# autofowl.net
KiCad netlist of a schematic drawn in EAGLE
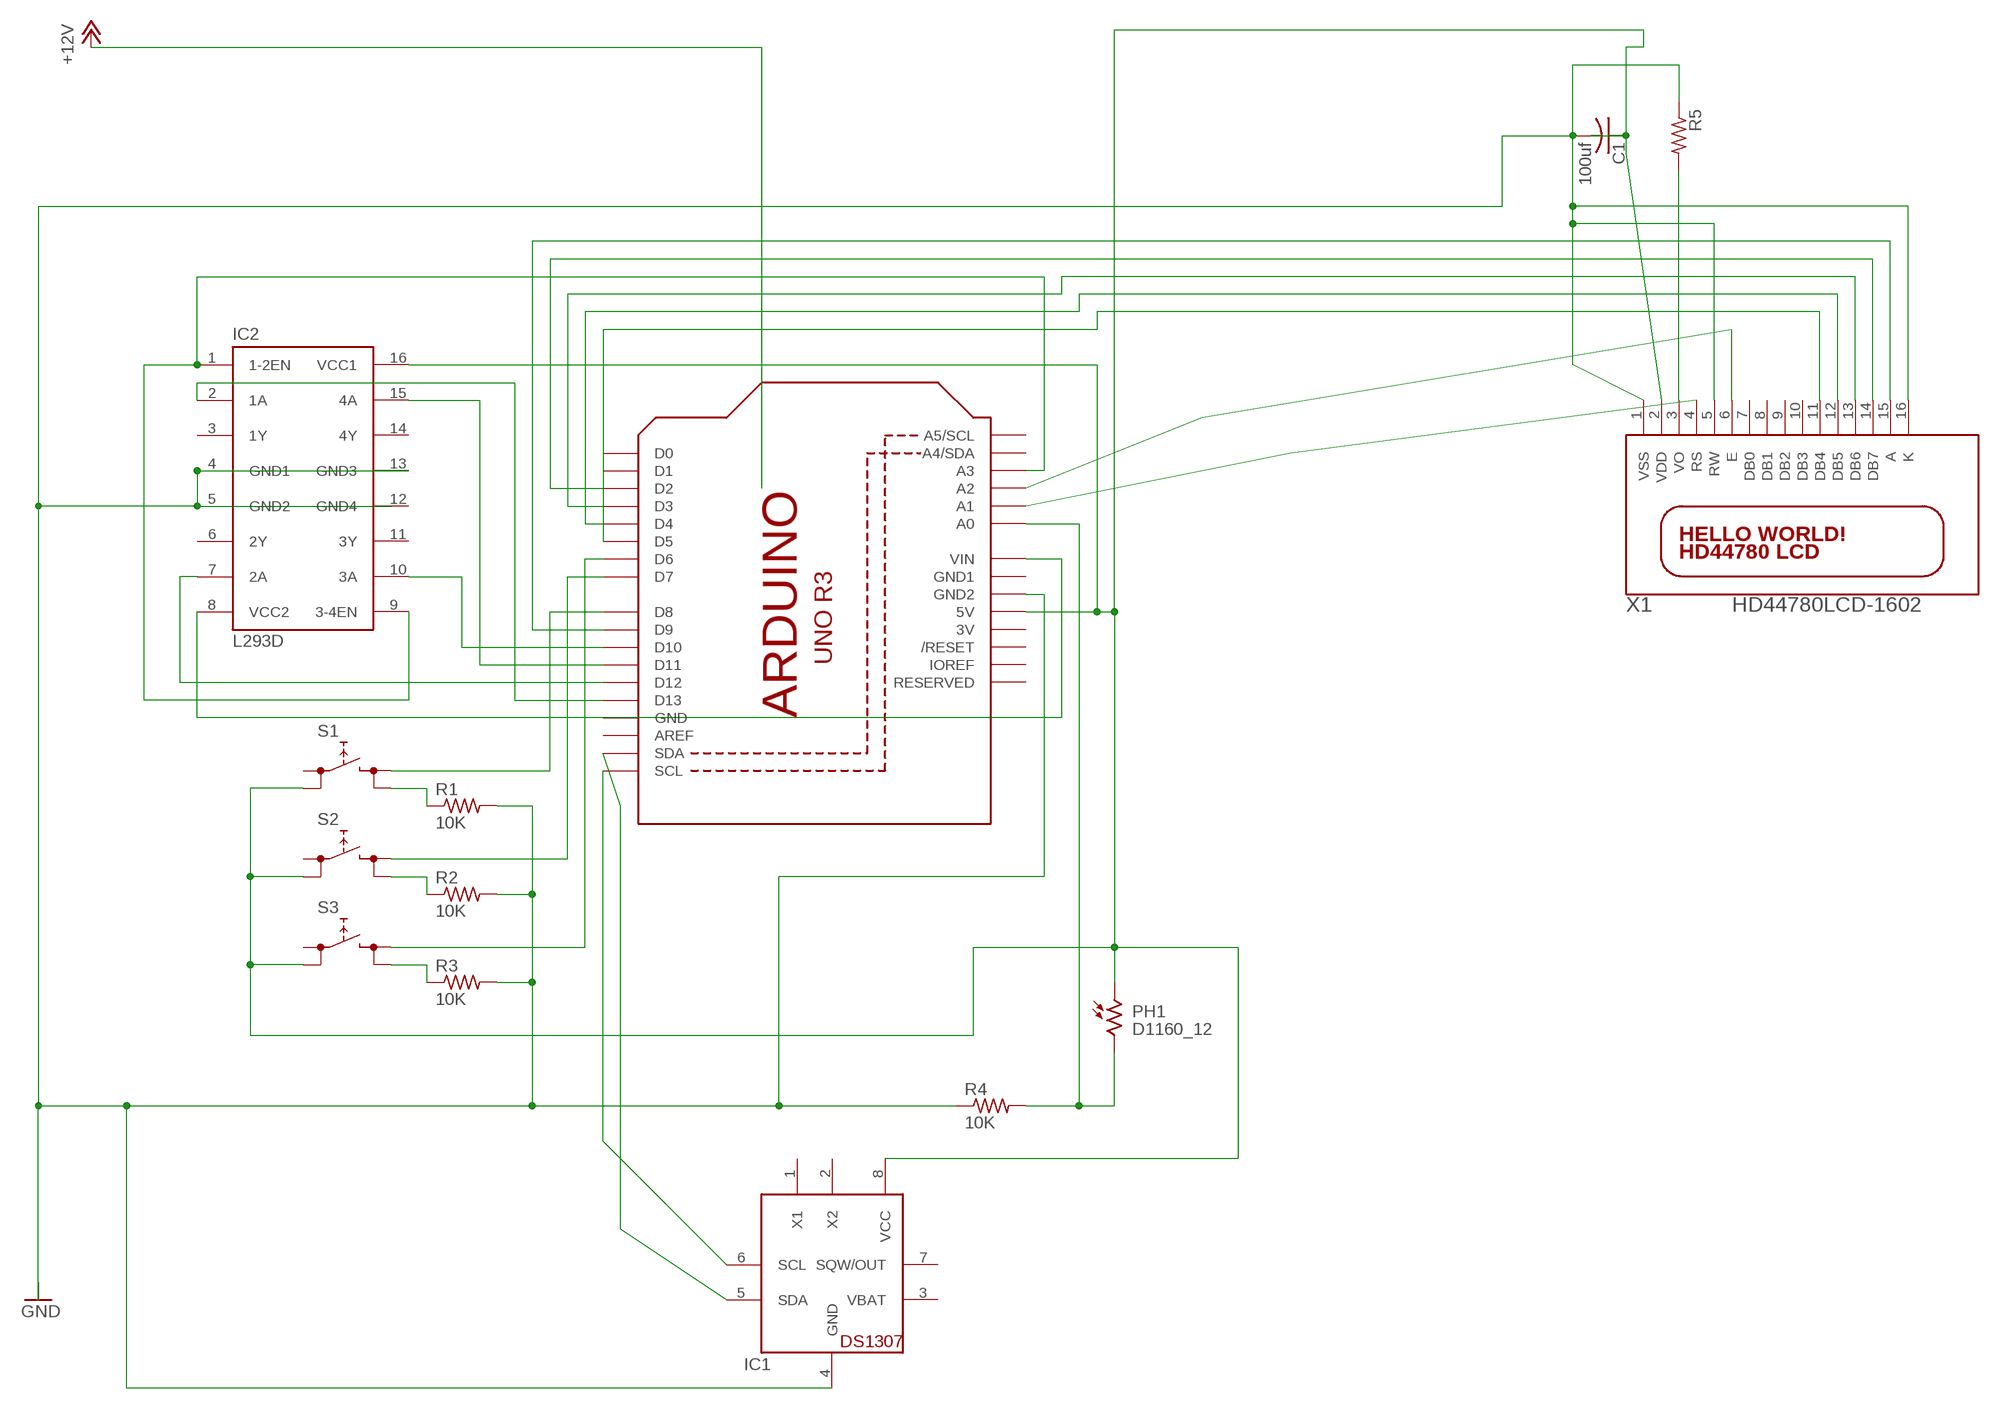
[diagram p0: schematic, sheet 1]

(export (version "E")
  (design (tool "Eeschema 10.0.6"))
  (components
    (comp (ref "C1")
      (value "100uf")
      (footprint "eagle-import:C050-024X044")
      (libsource (lib "eagle-import") (part "C-US050-024X044"))
    )
    (comp (ref "IC1")
      (value "DS1307")
      (footprint "eagle-import:DIL08")
      (libsource (lib "eagle-import") (part "DS1307"))
    )
    (comp (ref "IC2")
      (value "L293D")
      (footprint "eagle-import:DIL16")
      (libsource (lib "eagle-import") (part "L293D"))
    )
    (comp (ref "PH1")
      (value "D1160_12")
      (footprint "eagle-import:D11XX")
      (libsource (lib "eagle-import") (part "D1160_12"))
    )
    (comp (ref "R1")
      (value "10K")
      (footprint "eagle-import:0309_12")
      (libsource (lib "eagle-import") (part "R-US_0309/12"))
    )
    (comp (ref "R2")
      (value "10K")
      (footprint "eagle-import:0309_12")
      (libsource (lib "eagle-import") (part "R-US_0309/12"))
    )
    (comp (ref "R3")
      (value "10K")
      (footprint "eagle-import:0309_12")
      (libsource (lib "eagle-import") (part "R-US_0309/12"))
    )
    (comp (ref "R4")
      (value "10K")
      (footprint "eagle-import:0309_12")
      (libsource (lib "eagle-import") (part "R-US_0309/12"))
    )
    (comp (ref "R5")
      (value "R-US_0309/12")
      (footprint "eagle-import:0309_12")
      (libsource (lib "eagle-import") (part "R-US_0309/12"))
    )
    (comp (ref "S1")
      (value "REKN")
      (footprint "eagle-import:REKN")
      (libsource (lib "eagle-import") (part "REKN"))
    )
    (comp (ref "S2")
      (value "REKN")
      (footprint "eagle-import:REKN")
      (libsource (lib "eagle-import") (part "REKN"))
    )
    (comp (ref "S3")
      (value "REKN")
      (footprint "eagle-import:REKN")
      (libsource (lib "eagle-import") (part "REKN"))
    )
    (comp (ref "U1")
      (value "ARDUINOR3-DIMENSION")
      (footprint "eagle-import:ARDUINOR3")
      (libsource (lib "eagle-import") (part "ARDUINOR3-DIMENSION"))
    )
    (comp (ref "X1")
      (value "HD44780LCD-1602")
      (footprint "eagle-import:LCD1602")
      (libsource (lib "eagle-import") (part "HD44780LCD-1602"))
    )
  )
  (nets
    (net (code "2") (name "/3V") (class "Default")
      (node (ref "U1") (pin "3V") (pinfunction "3V_3V") (pintype "power_in"))
    )
    (net (code "3") (name "/GND1") (class "Default")
      (node (ref "U1") (pin "GND1") (pinfunction "GND1_GND1") (pintype "power_in"))
    )
    (net (code "4") (name "/GND4") (class "Default")
      (node (ref "IC2") (pin "12") (pinfunction "GND4_12") (pintype "power_in"))
    )
    (net (code "5") (name "/VBAT") (class "Default")
      (node (ref "IC1") (pin "3") (pinfunction "VBAT_3") (pintype "power_in"))
    )
    (net (code "6") (name "GND") (class "Default")
      (node (ref "U1") (pin "GND") (pinfunction "GND_GND") (pintype "power_in"))
    )
    (net (code "7") (name "Net-(IC1-GND)") (class "Default")
      (node (ref "C1") (pin "2") (pinfunction "2_2") (pintype "passive"))
      (node (ref "IC1") (pin "4") (pinfunction "GND_4") (pintype "power_in"))
      (node (ref "IC2") (pin "13") (pinfunction "GND3_13") (pintype "power_in"))
      (node (ref "IC2") (pin "4") (pinfunction "GND1_4") (pintype "power_in"))
      (node (ref "IC2") (pin "5") (pinfunction "GND2_5") (pintype "power_in"))
      (node (ref "R1") (pin "2") (pinfunction "2_2") (pintype "passive"))
      (node (ref "R2") (pin "2") (pinfunction "2_2") (pintype "passive"))
      (node (ref "R3") (pin "2") (pinfunction "2_2") (pintype "passive"))
      (node (ref "R4") (pin "1") (pinfunction "1_1") (pintype "passive"))
      (node (ref "R5") (pin "1") (pinfunction "1_1") (pintype "passive"))
      (node (ref "U1") (pin "GND2") (pinfunction "GND2_GND2") (pintype "power_in"))
      (node (ref "X1") (pin "1") (pinfunction "VSS_1") (pintype "power_in"))
      (node (ref "X1") (pin "16") (pinfunction "K_16") (pintype "input"))
      (node (ref "X1") (pin "5") (pinfunction "RW_5") (pintype "input"))
    )
    (net (code "8") (name "Net-(IC1-SCL)") (class "Default")
      (node (ref "IC1") (pin "6") (pinfunction "SCL_6") (pintype "bidirectional"))
      (node (ref "U1") (pin "SCL") (pinfunction "SCL_SCL") (pintype "bidirectional"))
    )
    (net (code "9") (name "Net-(IC1-SDA)") (class "Default")
      (node (ref "IC1") (pin "5") (pinfunction "SDA_5") (pintype "bidirectional"))
      (node (ref "U1") (pin "SDA") (pinfunction "SDA_SDA") (pintype "bidirectional"))
    )
    (net (code "10") (name "Net-(IC1-VCC)") (class "Default")
      (node (ref "C1") (pin "1") (pinfunction "1_1") (pintype "passive"))
      (node (ref "IC1") (pin "8") (pinfunction "VCC_8") (pintype "power_in"))
      (node (ref "IC2") (pin "16") (pinfunction "VCC1_16") (pintype "power_in"))
      (node (ref "PH1") (pin "1") (pinfunction "1_1") (pintype "passive"))
      (node (ref "S1") (pin "0B") (pinfunction "0_0B") (pintype "passive"))
      (node (ref "S2") (pin "0B") (pinfunction "0_0B") (pintype "passive"))
      (node (ref "S3") (pin "0B") (pinfunction "0_0B") (pintype "passive"))
      (node (ref "U1") (pin "5V") (pinfunction "5V_5V") (pintype "power_in"))
      (node (ref "X1") (pin "2") (pinfunction "VDD_2") (pintype "power_in"))
    )
    (net (code "11") (name "Net-(IC2-1-2EN)") (class "Default")
      (node (ref "IC2") (pin "1") (pinfunction "1-2EN_1") (pintype "input"))
      (node (ref "IC2") (pin "9") (pinfunction "3-4EN_9") (pintype "input"))
      (node (ref "U1") (pin "A3") (pinfunction "A3_A3") (pintype "bidirectional"))
    )
    (net (code "12") (name "Net-(IC2-1A)") (class "Default")
      (node (ref "IC2") (pin "2") (pinfunction "1A_2") (pintype "input"))
      (node (ref "U1") (pin "D13") (pinfunction "D13_D13") (pintype "bidirectional"))
    )
    (net (code "13") (name "Net-(IC2-2A)") (class "Default")
      (node (ref "IC2") (pin "7") (pinfunction "2A_7") (pintype "input"))
      (node (ref "U1") (pin "D12") (pinfunction "D12_D12") (pintype "bidirectional"))
    )
    (net (code "14") (name "Net-(IC2-3A)") (class "Default")
      (node (ref "IC2") (pin "10") (pinfunction "3A_10") (pintype "input"))
      (node (ref "U1") (pin "D10") (pinfunction "D10_D10") (pintype "bidirectional"))
    )
    (net (code "15") (name "Net-(IC2-4A)") (class "Default")
      (node (ref "IC2") (pin "15") (pinfunction "4A_15") (pintype "input"))
      (node (ref "U1") (pin "D11") (pinfunction "D11_D11") (pintype "bidirectional"))
    )
    (net (code "16") (name "Net-(IC2-VCC2)") (class "Default")
      (node (ref "IC2") (pin "8") (pinfunction "VCC2_8") (pintype "power_in"))
      (node (ref "U1") (pin "VIN") (pinfunction "VIN_VIN") (pintype "power_in"))
    )
    (net (code "17") (name "Net-(PH1-Pad2)") (class "Default")
      (node (ref "PH1") (pin "2") (pinfunction "2_2") (pintype "passive"))
      (node (ref "R4") (pin "2") (pinfunction "2_2") (pintype "passive"))
      (node (ref "U1") (pin "A0") (pinfunction "A0_A0") (pintype "bidirectional"))
    )
    (net (code "18") (name "Net-(R1-Pad1)") (class "Default")
      (node (ref "R1") (pin "1") (pinfunction "1_1") (pintype "passive"))
      (node (ref "S1") (pin "1B") (pinfunction "1_1B") (pintype "passive"))
    )
    (net (code "19") (name "Net-(R2-Pad1)") (class "Default")
      (node (ref "R2") (pin "1") (pinfunction "1_1") (pintype "passive"))
      (node (ref "S2") (pin "1B") (pinfunction "1_1B") (pintype "passive"))
    )
    (net (code "20") (name "Net-(R3-Pad1)") (class "Default")
      (node (ref "R3") (pin "1") (pinfunction "1_1") (pintype "passive"))
      (node (ref "S3") (pin "1B") (pinfunction "1_1B") (pintype "passive"))
    )
    (net (code "21") (name "Net-(S1-1-Pad1A)") (class "Default")
      (node (ref "S1") (pin "1A") (pinfunction "1_1A") (pintype "passive"))
      (node (ref "U1") (pin "D8") (pinfunction "D8_D8") (pintype "bidirectional"))
    )
    (net (code "22") (name "Net-(S2-1-Pad1A)") (class "Default")
      (node (ref "S2") (pin "1A") (pinfunction "1_1A") (pintype "passive"))
      (node (ref "U1") (pin "D7") (pinfunction "D7_D7") (pintype "bidirectional"))
    )
    (net (code "23") (name "Net-(S3-1-Pad1A)") (class "Default")
      (node (ref "S3") (pin "1A") (pinfunction "1_1A") (pintype "passive"))
      (node (ref "U1") (pin "D6") (pinfunction "D6_D6") (pintype "bidirectional"))
    )
    (net (code "24") (name "Net-(X1-A)") (class "Default")
      (node (ref "U1") (pin "D9") (pinfunction "D9_D9") (pintype "bidirectional"))
      (node (ref "X1") (pin "15") (pinfunction "A_15") (pintype "input"))
    )
    (net (code "25") (name "Net-(X1-DB4)") (class "Default")
      (node (ref "U1") (pin "D5") (pinfunction "D5_D5") (pintype "bidirectional"))
      (node (ref "X1") (pin "11") (pinfunction "DB4_11") (pintype "bidirectional"))
    )
    (net (code "26") (name "Net-(X1-DB5)") (class "Default")
      (node (ref "U1") (pin "D4") (pinfunction "D4_D4") (pintype "bidirectional"))
      (node (ref "X1") (pin "12") (pinfunction "DB5_12") (pintype "bidirectional"))
    )
    (net (code "27") (name "Net-(X1-DB6)") (class "Default")
      (node (ref "U1") (pin "D3") (pinfunction "D3_D3") (pintype "bidirectional"))
      (node (ref "X1") (pin "13") (pinfunction "DB6_13") (pintype "bidirectional"))
    )
    (net (code "28") (name "Net-(X1-DB7)") (class "Default")
      (node (ref "U1") (pin "D2") (pinfunction "D2_D2") (pintype "bidirectional"))
      (node (ref "X1") (pin "14") (pinfunction "DB7_14") (pintype "bidirectional"))
    )
    (net (code "29") (name "Net-(X1-E)") (class "Default")
      (node (ref "U1") (pin "A2") (pinfunction "A2_A2") (pintype "bidirectional"))
      (node (ref "X1") (pin "6") (pinfunction "E_6") (pintype "input"))
    )
    (net (code "30") (name "Net-(X1-RS)") (class "Default")
      (node (ref "U1") (pin "A1") (pinfunction "A1_A1") (pintype "bidirectional"))
      (node (ref "X1") (pin "4") (pinfunction "RS_4") (pintype "input"))
    )
    (net (code "31") (name "Net-(X1-VO)") (class "Default")
      (node (ref "R5") (pin "2") (pinfunction "2_2") (pintype "passive"))
      (node (ref "X1") (pin "3") (pinfunction "VO_3") (pintype "input"))
    )
    (net (code "32") (name "unconnected-(IC1-SQW{slash}OUT-Pad7)") (class "Default")
      (node (ref "IC1") (pin "7") (pinfunction "SQW/OUT_7") (pintype "bidirectional"))
    )
    (net (code "33") (name "unconnected-(IC1-X1-Pad1)") (class "Default")
      (node (ref "IC1") (pin "1") (pinfunction "X1_1") (pintype "passive"))
    )
    (net (code "34") (name "unconnected-(IC1-X2-Pad2)") (class "Default")
      (node (ref "IC1") (pin "2") (pinfunction "X2_2") (pintype "passive"))
    )
    (net (code "35") (name "unconnected-(IC2-1Y-Pad3)") (class "Default")
      (node (ref "IC2") (pin "3") (pinfunction "1Y_3") (pintype "output"))
    )
    (net (code "36") (name "unconnected-(IC2-2Y-Pad6)") (class "Default")
      (node (ref "IC2") (pin "6") (pinfunction "2Y_6") (pintype "output"))
    )
    (net (code "37") (name "unconnected-(IC2-3Y-Pad11)") (class "Default")
      (node (ref "IC2") (pin "11") (pinfunction "3Y_11") (pintype "output"))
    )
    (net (code "38") (name "unconnected-(IC2-4Y-Pad14)") (class "Default")
      (node (ref "IC2") (pin "14") (pinfunction "4Y_14") (pintype "output"))
    )
    (net (code "39") (name "unconnected-(S1-0-Pad0A)") (class "Default")
      (node (ref "S1") (pin "0A") (pinfunction "0_0A") (pintype "passive"))
    )
    (net (code "40") (name "unconnected-(S2-0-Pad0A)") (class "Default")
      (node (ref "S2") (pin "0A") (pinfunction "0_0A") (pintype "passive"))
    )
    (net (code "41") (name "unconnected-(S3-0-Pad0A)") (class "Default")
      (node (ref "S3") (pin "0A") (pinfunction "0_0A") (pintype "passive"))
    )
    (net (code "42") (name "unconnected-(U1-A4{slash}SDA-PadA4)") (class "Default")
      (node (ref "U1") (pin "A4") (pinfunction "A4/SDA_A4") (pintype "bidirectional"))
    )
    (net (code "43") (name "unconnected-(U1-A5{slash}SCL-PadA5)") (class "Default")
      (node (ref "U1") (pin "A5") (pinfunction "A5/SCL_A5") (pintype "bidirectional"))
    )
    (net (code "44") (name "unconnected-(U1-PadAREF)") (class "Default")
      (node (ref "U1") (pin "AREF") (pinfunction "AREF_AREF") (pintype "bidirectional"))
    )
    (net (code "45") (name "unconnected-(U1-PadD0)") (class "Default")
      (node (ref "U1") (pin "D0") (pinfunction "D0_D0") (pintype "bidirectional"))
    )
    (net (code "46") (name "unconnected-(U1-PadD1)") (class "Default")
      (node (ref "U1") (pin "D1") (pinfunction "D1_D1") (pintype "bidirectional"))
    )
    (net (code "47") (name "unconnected-(U1-PadIOREF)") (class "Default")
      (node (ref "U1") (pin "IOREF") (pinfunction "IOREF_IOREF") (pintype "output"))
    )
    (net (code "48") (name "unconnected-(U1-PadRESERVED)") (class "Default")
      (node (ref "U1") (pin "RESERVED") (pinfunction "RESERVED_RESERVED") (pintype "no_connect"))
    )
    (net (code "49") (name "unconnected-(U1-{slash}RESET-PadRESET)") (class "Default")
      (node (ref "U1") (pin "RESET") (pinfunction "/RESET_RESET") (pintype "bidirectional"))
    )
    (net (code "50") (name "unconnected-(X1-DB0-Pad7)") (class "Default")
      (node (ref "X1") (pin "7") (pinfunction "DB0_7") (pintype "bidirectional"))
    )
    (net (code "51") (name "unconnected-(X1-DB1-Pad8)") (class "Default")
      (node (ref "X1") (pin "8") (pinfunction "DB1_8") (pintype "bidirectional"))
    )
    (net (code "52") (name "unconnected-(X1-DB2-Pad9)") (class "Default")
      (node (ref "X1") (pin "9") (pinfunction "DB2_9") (pintype "bidirectional"))
    )
    (net (code "53") (name "unconnected-(X1-DB3-Pad10)") (class "Default")
      (node (ref "X1") (pin "10") (pinfunction "DB3_10") (pintype "bidirectional"))
    )
  )
)
